# R450B.net
KiCad netlist of a schematic drawn in EAGLE
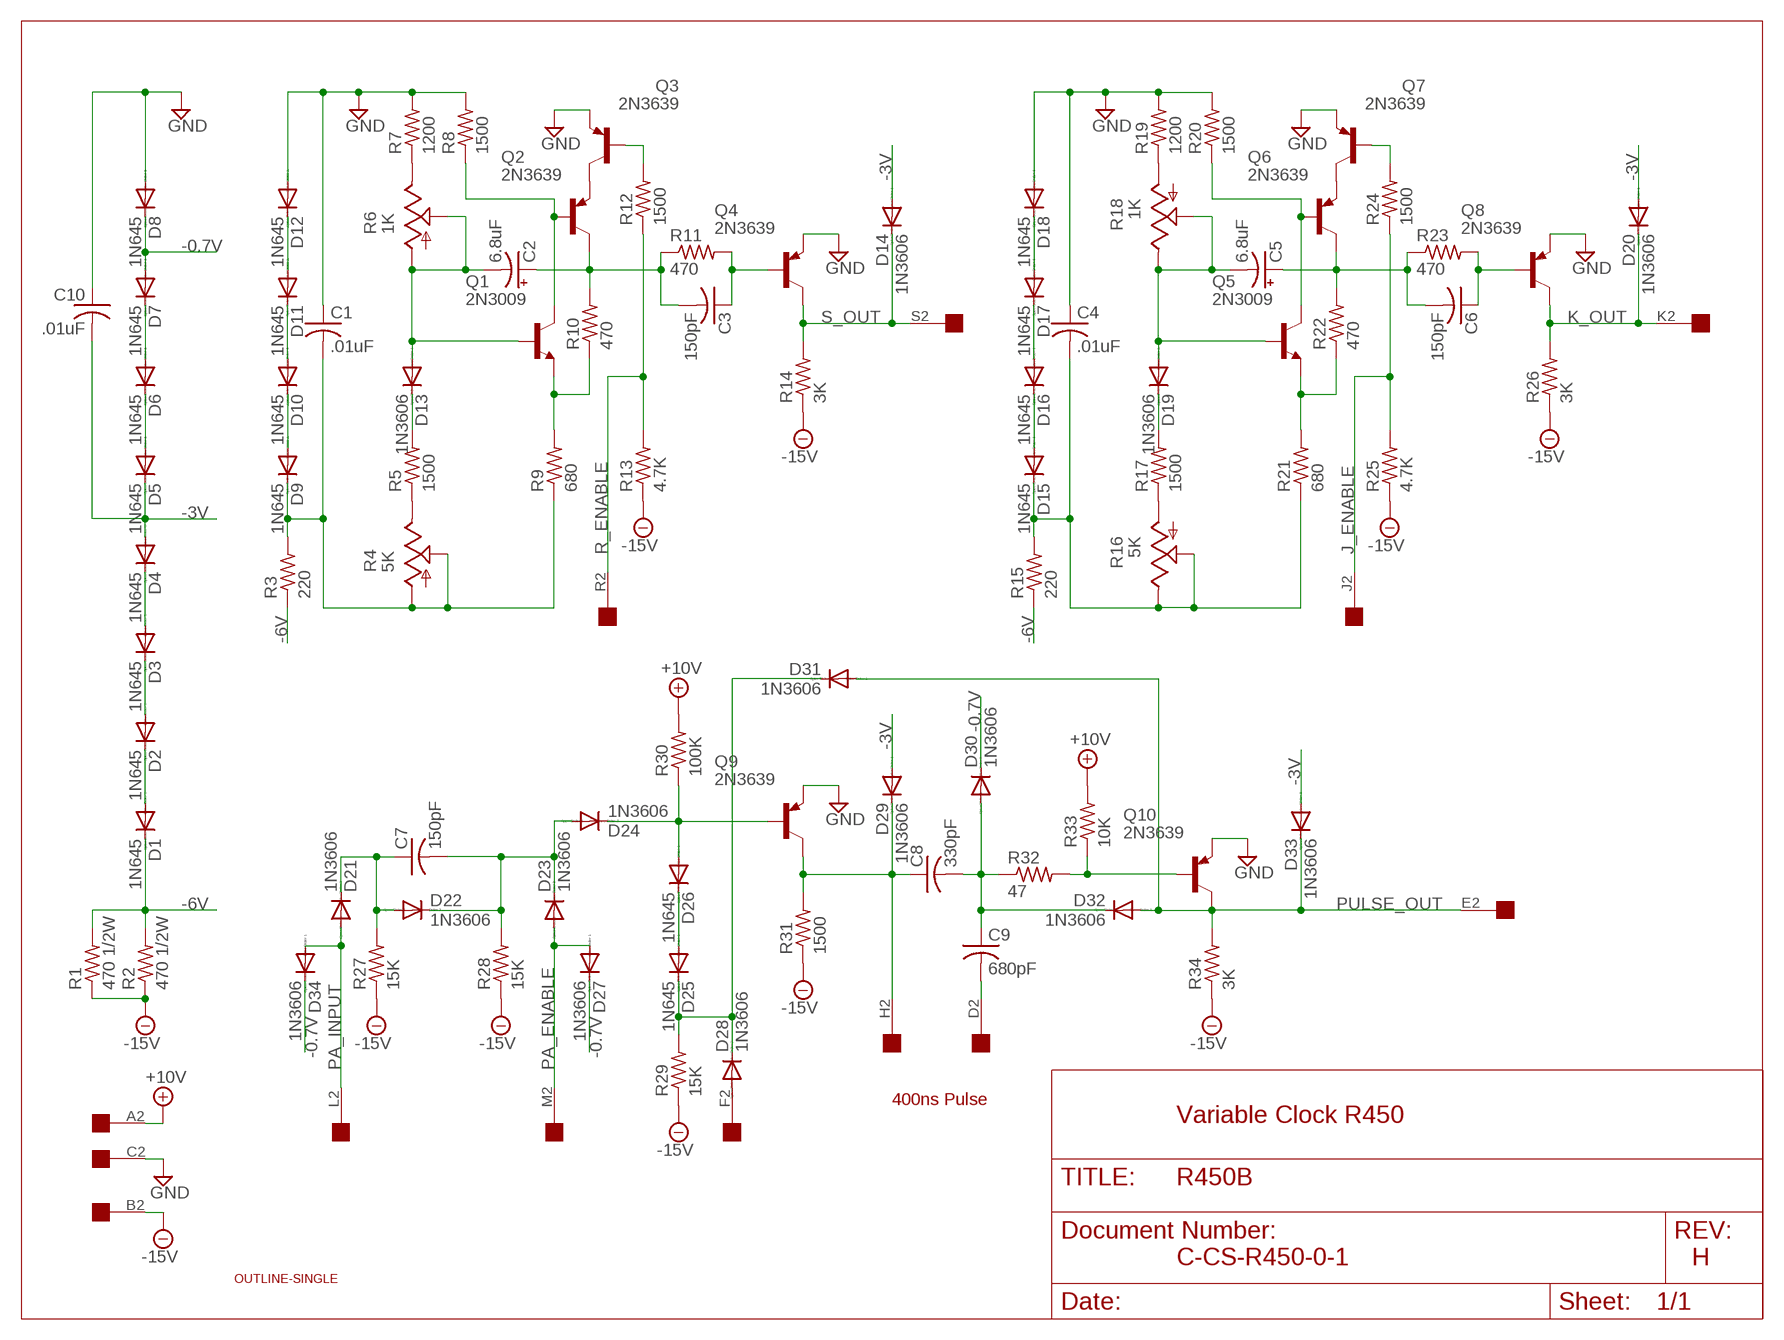
[diagram p0: schematic, sheet 1]

(export (version "E")
  (design (tool "Eeschema 10.0.6"))
  (components
    (comp (ref "C1")
      (value ".01uF")
      (footprint "eagle-import:C063-025X075")
      (libsource (lib "eagle-import") (part "C-US"))
    )
    (comp (ref "C2")
      (value "6.8uF")
      (footprint "eagle-import:E15-5")
      (libsource (lib "eagle-import") (part "CPOL-USE15-5AXIAL"))
    )
    (comp (ref "C3")
      (value "150pF")
      (footprint "eagle-import:C075-032X103")
      (libsource (lib "eagle-import") (part "C-US075-032X103"))
    )
    (comp (ref "C4")
      (value ".01uF")
      (footprint "eagle-import:C063-025X075")
      (libsource (lib "eagle-import") (part "C-US"))
    )
    (comp (ref "C5")
      (value "6.8uF")
      (footprint "eagle-import:E15-5")
      (libsource (lib "eagle-import") (part "CPOL-USE15-5AXIAL"))
    )
    (comp (ref "C6")
      (value "150pF")
      (footprint "eagle-import:C063-025X075")
      (libsource (lib "eagle-import") (part "C-US"))
    )
    (comp (ref "C7")
      (value "150pF")
      (footprint "eagle-import:C063-025X075")
      (libsource (lib "eagle-import") (part "C-US"))
    )
    (comp (ref "C8")
      (value "330pF")
      (footprint "eagle-import:C063-025X075")
      (libsource (lib "eagle-import") (part "C-US"))
    )
    (comp (ref "C9")
      (value "680pF")
      (footprint "eagle-import:C063-025X075")
      (libsource (lib "eagle-import") (part "C-US"))
    )
    (comp (ref "C10")
      (value ".01uF")
      (footprint "eagle-import:C063-025X075")
      (libsource (lib "eagle-import") (part "C-US"))
    )
    (comp (ref "D1")
      (value "1N645")
      (footprint "eagle-import:DO35-10")
      (libsource (lib "eagle-import") (part "1N4148DO35-10"))
    )
    (comp (ref "D2")
      (value "1N645")
      (footprint "eagle-import:DO35-10")
      (libsource (lib "eagle-import") (part "1N4148DO35-10"))
    )
    (comp (ref "D3")
      (value "1N645")
      (footprint "eagle-import:DO35-10")
      (libsource (lib "eagle-import") (part "1N4148DO35-10"))
    )
    (comp (ref "D4")
      (value "1N645")
      (footprint "eagle-import:DO35-10")
      (libsource (lib "eagle-import") (part "1N4148DO35-10"))
    )
    (comp (ref "D5")
      (value "1N645")
      (footprint "eagle-import:DO35-10")
      (libsource (lib "eagle-import") (part "1N4148DO35-10"))
    )
    (comp (ref "D6")
      (value "1N645")
      (footprint "eagle-import:DO35-10")
      (libsource (lib "eagle-import") (part "1N4148DO35-10"))
    )
    (comp (ref "D7")
      (value "1N645")
      (footprint "eagle-import:DO35-10")
      (libsource (lib "eagle-import") (part "1N4148DO35-10"))
    )
    (comp (ref "D8")
      (value "1N645")
      (footprint "eagle-import:DO35-10")
      (libsource (lib "eagle-import") (part "1N4148DO35-10"))
    )
    (comp (ref "D9")
      (value "1N645")
      (footprint "eagle-import:DO35-10")
      (libsource (lib "eagle-import") (part "1N4148DO35-10"))
    )
    (comp (ref "D10")
      (value "1N645")
      (footprint "eagle-import:DO35-10")
      (libsource (lib "eagle-import") (part "1N4148DO35-10"))
    )
    (comp (ref "D11")
      (value "1N645")
      (footprint "eagle-import:DO35-10")
      (libsource (lib "eagle-import") (part "1N4148DO35-10"))
    )
    (comp (ref "D12")
      (value "1N645")
      (footprint "eagle-import:DO35-10")
      (libsource (lib "eagle-import") (part "1N4148DO35-10"))
    )
    (comp (ref "D13")
      (value "1N3606")
      (footprint "eagle-import:DO35-10")
      (libsource (lib "eagle-import") (part "1N4148DO35-10"))
    )
    (comp (ref "D14")
      (value "1N3606")
      (footprint "eagle-import:DO35-10")
      (libsource (lib "eagle-import") (part "1N4148DO35-10"))
    )
    (comp (ref "D15")
      (value "1N645")
      (footprint "eagle-import:DO35-10")
      (libsource (lib "eagle-import") (part "1N4148DO35-10"))
    )
    (comp (ref "D16")
      (value "1N645")
      (footprint "eagle-import:DO35-10")
      (libsource (lib "eagle-import") (part "1N4148DO35-10"))
    )
    (comp (ref "D17")
      (value "1N645")
      (footprint "eagle-import:DO35-10")
      (libsource (lib "eagle-import") (part "1N4148DO35-10"))
    )
    (comp (ref "D18")
      (value "1N645")
      (footprint "eagle-import:DO35-10")
      (libsource (lib "eagle-import") (part "1N4148DO35-10"))
    )
    (comp (ref "D19")
      (value "1N3606")
      (footprint "eagle-import:DO35-10")
      (libsource (lib "eagle-import") (part "1N4148DO35-10"))
    )
    (comp (ref "D20")
      (value "1N3606")
      (footprint "eagle-import:DO35-10")
      (libsource (lib "eagle-import") (part "1N4148DO35-10"))
    )
    (comp (ref "D21")
      (value "1N3606")
      (footprint "eagle-import:DO35-10")
      (libsource (lib "eagle-import") (part "1N4148DO35-10"))
    )
    (comp (ref "D22")
      (value "1N3606")
      (footprint "eagle-import:DO35-10")
      (libsource (lib "eagle-import") (part "1N4148DO35-10"))
    )
    (comp (ref "D23")
      (value "1N3606")
      (footprint "eagle-import:DO35-10")
      (libsource (lib "eagle-import") (part "1N4148DO35-10"))
    )
    (comp (ref "D24")
      (value "1N3606")
      (footprint "eagle-import:DO35-10")
      (libsource (lib "eagle-import") (part "1N4148DO35-10"))
    )
    (comp (ref "D25")
      (value "1N645")
      (footprint "eagle-import:DO35-10")
      (libsource (lib "eagle-import") (part "1N4148DO35-10"))
    )
    (comp (ref "D26")
      (value "1N645")
      (footprint "eagle-import:DO35-10")
      (libsource (lib "eagle-import") (part "1N4148DO35-10"))
    )
    (comp (ref "D27")
      (value "1N3606")
      (footprint "eagle-import:DO35-10")
      (libsource (lib "eagle-import") (part "1N4148DO35-10"))
    )
    (comp (ref "D28")
      (value "1N3606")
      (footprint "eagle-import:DO35-10")
      (libsource (lib "eagle-import") (part "1N4148DO35-10"))
    )
    (comp (ref "D29")
      (value "1N3606")
      (footprint "eagle-import:DO35-10")
      (libsource (lib "eagle-import") (part "1N4148DO35-10"))
    )
    (comp (ref "D30")
      (value "1N3606")
      (footprint "eagle-import:DO35-10")
      (libsource (lib "eagle-import") (part "1N4148DO35-10"))
    )
    (comp (ref "D31")
      (value "1N3606")
      (footprint "eagle-import:DO35-10")
      (libsource (lib "eagle-import") (part "1N4148DO35-10"))
    )
    (comp (ref "D32")
      (value "1N3606")
      (footprint "eagle-import:DO35-10")
      (libsource (lib "eagle-import") (part "1N4148DO35-10"))
    )
    (comp (ref "D33")
      (value "1N3606")
      (footprint "eagle-import:DO35-10")
      (libsource (lib "eagle-import") (part "1N4148DO35-10"))
    )
    (comp (ref "D34")
      (value "1N3606")
      (footprint "eagle-import:DO35-10")
      (libsource (lib "eagle-import") (part "1N4148DO35-10"))
    )
    (comp (ref "Q1")
      (value "2N3009")
      (footprint "eagle-import:TO5")
      (libsource (lib "eagle-import") (part "2N2102"))
    )
    (comp (ref "Q2")
      (value "2N3639")
      (footprint "eagle-import:TO39")
      (libsource (lib "eagle-import") (part "2N2904"))
    )
    (comp (ref "Q3")
      (value "2N3639")
      (footprint "eagle-import:TO39")
      (libsource (lib "eagle-import") (part "2N2904"))
    )
    (comp (ref "Q4")
      (value "2N3639")
      (footprint "eagle-import:TO39")
      (libsource (lib "eagle-import") (part "2N2904"))
    )
    (comp (ref "Q5")
      (value "2N3009")
      (footprint "eagle-import:TO5")
      (libsource (lib "eagle-import") (part "2N2102"))
    )
    (comp (ref "Q6")
      (value "2N3639")
      (footprint "eagle-import:TO39")
      (libsource (lib "eagle-import") (part "2N2904"))
    )
    (comp (ref "Q7")
      (value "2N3639")
      (footprint "eagle-import:TO39")
      (libsource (lib "eagle-import") (part "2N2904"))
    )
    (comp (ref "Q8")
      (value "2N3639")
      (footprint "eagle-import:TO39")
      (libsource (lib "eagle-import") (part "2N2904"))
    )
    (comp (ref "Q9")
      (value "2N3639")
      (footprint "eagle-import:TO39")
      (libsource (lib "eagle-import") (part "2N2904"))
    )
    (comp (ref "Q10")
      (value "2N3639")
      (footprint "eagle-import:TO39")
      (libsource (lib "eagle-import") (part "2N2904"))
    )
    (comp (ref "R1")
      (value "470 1/2W")
      (footprint "eagle-import:0411_15")
      (libsource (lib "eagle-import") (part "R-US_0411/15"))
    )
    (comp (ref "R2")
      (value "470 1/2W")
      (footprint "eagle-import:0411_15")
      (libsource (lib "eagle-import") (part "R-US_0411/15"))
    )
    (comp (ref "R3")
      (value "220")
      (footprint "eagle-import:0207_10")
      (libsource (lib "eagle-import") (part "R-US_0207/10"))
    )
    (comp (ref "R4")
      (value "5K")
      (footprint "eagle-import:CT6")
      (libsource (lib "eagle-import") (part "TRIM_US-CT6"))
    )
    (comp (ref "R5")
      (value "1500")
      (footprint "eagle-import:0207_10")
      (libsource (lib "eagle-import") (part "R-US_0207/10"))
    )
    (comp (ref "R6")
      (value "1K")
      (footprint "eagle-import:CT6")
      (libsource (lib "eagle-import") (part "TRIM_US-CT6"))
    )
    (comp (ref "R7")
      (value "1200")
      (footprint "eagle-import:0207_10")
      (libsource (lib "eagle-import") (part "R-US_0207/10"))
    )
    (comp (ref "R8")
      (value "1500")
      (footprint "eagle-import:0207_10")
      (libsource (lib "eagle-import") (part "R-US_0207/10"))
    )
    (comp (ref "R9")
      (value "680")
      (footprint "eagle-import:0207_10")
      (libsource (lib "eagle-import") (part "R-US_0207/10"))
    )
    (comp (ref "R10")
      (value "470")
      (footprint "eagle-import:0207_10")
      (libsource (lib "eagle-import") (part "R-US_0207/10"))
    )
    (comp (ref "R11")
      (value "470")
      (footprint "eagle-import:0207_10")
      (libsource (lib "eagle-import") (part "R-US_0207/10"))
    )
    (comp (ref "R12")
      (value "1500")
      (footprint "eagle-import:0207_10")
      (libsource (lib "eagle-import") (part "R-US_0207/10"))
    )
    (comp (ref "R13")
      (value "4.7K")
      (footprint "eagle-import:0207_10")
      (libsource (lib "eagle-import") (part "R-US_0207/10"))
    )
    (comp (ref "R14")
      (value "3K")
      (footprint "eagle-import:0207_10")
      (libsource (lib "eagle-import") (part "R-US_0207/10"))
    )
    (comp (ref "R15")
      (value "220")
      (footprint "eagle-import:0207_10")
      (libsource (lib "eagle-import") (part "R-US_0207/10"))
    )
    (comp (ref "R16")
      (value "5K")
      (footprint "eagle-import:CT6")
      (libsource (lib "eagle-import") (part "TRIM_US-CT6"))
    )
    (comp (ref "R17")
      (value "1500")
      (footprint "eagle-import:0207_10")
      (libsource (lib "eagle-import") (part "R-US_0207/10"))
    )
    (comp (ref "R18")
      (value "1K")
      (footprint "eagle-import:CT6")
      (libsource (lib "eagle-import") (part "TRIM_US-CT6"))
    )
    (comp (ref "R19")
      (value "1200")
      (footprint "eagle-import:0207_10")
      (libsource (lib "eagle-import") (part "R-US_0207/10"))
    )
    (comp (ref "R20")
      (value "1500")
      (footprint "eagle-import:0207_10")
      (libsource (lib "eagle-import") (part "R-US_0207/10"))
    )
    (comp (ref "R21")
      (value "680")
      (footprint "eagle-import:0207_10")
      (libsource (lib "eagle-import") (part "R-US_0207/10"))
    )
    (comp (ref "R22")
      (value "470")
      (footprint "eagle-import:0207_10")
      (libsource (lib "eagle-import") (part "R-US_0207/10"))
    )
    (comp (ref "R23")
      (value "470")
      (footprint "eagle-import:0207_10")
      (libsource (lib "eagle-import") (part "R-US_0207/10"))
    )
    (comp (ref "R24")
      (value "1500")
      (footprint "eagle-import:0207_10")
      (libsource (lib "eagle-import") (part "R-US_0207/10"))
    )
    (comp (ref "R25")
      (value "4.7K")
      (footprint "eagle-import:0207_10")
      (libsource (lib "eagle-import") (part "R-US_0207/10"))
    )
    (comp (ref "R26")
      (value "3K")
      (footprint "eagle-import:0207_10")
      (libsource (lib "eagle-import") (part "R-US_0207/10"))
    )
    (comp (ref "R27")
      (value "15K")
      (footprint "eagle-import:0207_10")
      (libsource (lib "eagle-import") (part "R-US_0207/10"))
    )
    (comp (ref "R28")
      (value "15K")
      (footprint "eagle-import:0207_10")
      (libsource (lib "eagle-import") (part "R-US_0207/10"))
    )
    (comp (ref "R29")
      (value "15K")
      (footprint "eagle-import:0207_10")
      (libsource (lib "eagle-import") (part "R-US_0207/10"))
    )
    (comp (ref "R30")
      (value "100K")
      (footprint "eagle-import:0207_10")
      (libsource (lib "eagle-import") (part "R-US_0207/10"))
    )
    (comp (ref "R31")
      (value "1500")
      (footprint "eagle-import:0207_10")
      (libsource (lib "eagle-import") (part "R-US_0207/10"))
    )
    (comp (ref "R32")
      (value "47")
      (footprint "eagle-import:0207_10")
      (libsource (lib "eagle-import") (part "R-US_0207/10"))
    )
    (comp (ref "R33")
      (value "10K")
      (footprint "eagle-import:0207_10")
      (libsource (lib "eagle-import") (part "R-US_0207/10"))
    )
    (comp (ref "R34")
      (value "3K")
      (footprint "eagle-import:0207_10")
      (libsource (lib "eagle-import") (part "R-US_0207/10"))
    )
    (comp (ref "U$1")
      (value "OUTLINE-SINGLE")
      (footprint "eagle-import:SINGLE")
      (libsource (lib "eagle-import") (part "OUTLINE-SINGLE"))
    )
    (comp (ref "U$2")
      (value "EDGE-1")
      (footprint "eagle-import:EDGE-CON1")
      (libsource (lib "eagle-import") (part "EDGE-1"))
    )
  )
  (nets
    (net (code "1") (name "+10V") (class "Default")
      (node (ref "R30") (pin "2") (pinfunction "2_2") (pintype "passive"))
      (node (ref "R33") (pin "2") (pinfunction "2_2") (pintype "passive"))
      (node (ref "U$2") (pin "A2") (pinfunction "1_A2") (pintype "bidirectional"))
    )
    (net (code "2") (name "-15V") (class "Default")
      (node (ref "R1") (pin "1") (pinfunction "1_1") (pintype "passive"))
      (node (ref "R13") (pin "1") (pinfunction "1_1") (pintype "passive"))
      (node (ref "R14") (pin "1") (pinfunction "1_1") (pintype "passive"))
      (node (ref "R2") (pin "1") (pinfunction "1_1") (pintype "passive"))
      (node (ref "R25") (pin "1") (pinfunction "1_1") (pintype "passive"))
      (node (ref "R26") (pin "1") (pinfunction "1_1") (pintype "passive"))
      (node (ref "R27") (pin "1") (pinfunction "1_1") (pintype "passive"))
      (node (ref "R28") (pin "1") (pinfunction "1_1") (pintype "passive"))
      (node (ref "R29") (pin "1") (pinfunction "1_1") (pintype "passive"))
      (node (ref "R31") (pin "1") (pinfunction "1_1") (pintype "passive"))
      (node (ref "R34") (pin "1") (pinfunction "1_1") (pintype "passive"))
      (node (ref "U$2") (pin "B2") (pinfunction "1_B2") (pintype "bidirectional"))
    )
    (net (code "3") (name "/-0.7V") (class "Default")
      (node (ref "D27") (pin "C") (pinfunction "C_C") (pintype "passive"))
      (node (ref "D30") (pin "C") (pinfunction "C_C") (pintype "passive"))
      (node (ref "D34") (pin "C") (pinfunction "C_C") (pintype "passive"))
      (node (ref "D7") (pin "A") (pinfunction "A_A") (pintype "passive"))
      (node (ref "D8") (pin "C") (pinfunction "C_C") (pintype "passive"))
    )
    (net (code "4") (name "/-3V") (class "Default")
      (node (ref "C10") (pin "2") (pinfunction "2_2") (pintype "passive"))
      (node (ref "D14") (pin "A") (pinfunction "A_A") (pintype "passive"))
      (node (ref "D20") (pin "A") (pinfunction "A_A") (pintype "passive"))
      (node (ref "D29") (pin "A") (pinfunction "A_A") (pintype "passive"))
      (node (ref "D33") (pin "A") (pinfunction "A_A") (pintype "passive"))
      (node (ref "D4") (pin "A") (pinfunction "A_A") (pintype "passive"))
      (node (ref "D5") (pin "C") (pinfunction "C_C") (pintype "passive"))
    )
    (net (code "5") (name "/-6V") (class "Default")
      (node (ref "D1") (pin "C") (pinfunction "C_C") (pintype "passive"))
      (node (ref "R1") (pin "2") (pinfunction "2_2") (pintype "passive"))
      (node (ref "R15") (pin "1") (pinfunction "1_1") (pintype "passive"))
      (node (ref "R2") (pin "2") (pinfunction "2_2") (pintype "passive"))
      (node (ref "R3") (pin "1") (pinfunction "1_1") (pintype "passive"))
    )
    (net (code "6") (name "/J_ENABLE") (class "Default")
      (node (ref "R24") (pin "1") (pinfunction "1_1") (pintype "passive"))
      (node (ref "R25") (pin "2") (pinfunction "2_2") (pintype "passive"))
      (node (ref "U$2") (pin "J2") (pinfunction "1_J2") (pintype "bidirectional"))
    )
    (net (code "7") (name "/K_OUT") (class "Default")
      (node (ref "D20") (pin "C") (pinfunction "C_C") (pintype "passive"))
      (node (ref "Q8") (pin "3") (pinfunction "C_3") (pintype "passive"))
      (node (ref "R26") (pin "2") (pinfunction "2_2") (pintype "passive"))
      (node (ref "U$2") (pin "K2") (pinfunction "1_K2") (pintype "bidirectional"))
    )
    (net (code "8") (name "/PA_ENABLE") (class "Default")
      (node (ref "D23") (pin "A") (pinfunction "A_A") (pintype "passive"))
      (node (ref "D27") (pin "A") (pinfunction "A_A") (pintype "passive"))
      (node (ref "U$2") (pin "M2") (pinfunction "1_M2") (pintype "bidirectional"))
    )
    (net (code "9") (name "/PA_INPUT") (class "Default")
      (node (ref "D21") (pin "A") (pinfunction "A_A") (pintype "passive"))
      (node (ref "D34") (pin "A") (pinfunction "A_A") (pintype "passive"))
      (node (ref "U$2") (pin "L2") (pinfunction "1_L2") (pintype "bidirectional"))
    )
    (net (code "10") (name "/PULSE_OUT") (class "Default")
      (node (ref "D31") (pin "A") (pinfunction "A_A") (pintype "passive"))
      (node (ref "D32") (pin "A") (pinfunction "A_A") (pintype "passive"))
      (node (ref "D33") (pin "C") (pinfunction "C_C") (pintype "passive"))
      (node (ref "Q10") (pin "3") (pinfunction "C_3") (pintype "passive"))
      (node (ref "R34") (pin "2") (pinfunction "2_2") (pintype "passive"))
      (node (ref "U$2") (pin "E2") (pinfunction "1_E2") (pintype "bidirectional"))
    )
    (net (code "11") (name "/R_ENABLE") (class "Default")
      (node (ref "R12") (pin "1") (pinfunction "1_1") (pintype "passive"))
      (node (ref "R13") (pin "2") (pinfunction "2_2") (pintype "passive"))
      (node (ref "U$2") (pin "R2") (pinfunction "1_R2") (pintype "bidirectional"))
    )
    (net (code "12") (name "/S_OUT") (class "Default")
      (node (ref "D14") (pin "C") (pinfunction "C_C") (pintype "passive"))
      (node (ref "Q4") (pin "3") (pinfunction "C_3") (pintype "passive"))
      (node (ref "R14") (pin "2") (pinfunction "2_2") (pintype "passive"))
      (node (ref "U$2") (pin "S2") (pinfunction "1_S2") (pintype "bidirectional"))
    )
    (net (code "13") (name "GND") (class "Default")
      (node (ref "C1") (pin "1") (pinfunction "1_1") (pintype "passive"))
      (node (ref "C10") (pin "1") (pinfunction "1_1") (pintype "passive"))
      (node (ref "C4") (pin "1") (pinfunction "1_1") (pintype "passive"))
      (node (ref "D12") (pin "A") (pinfunction "A_A") (pintype "passive"))
      (node (ref "D18") (pin "A") (pinfunction "A_A") (pintype "passive"))
      (node (ref "D8") (pin "A") (pinfunction "A_A") (pintype "passive"))
      (node (ref "Q10") (pin "1") (pinfunction "E_1") (pintype "passive"))
      (node (ref "Q3") (pin "1") (pinfunction "E_1") (pintype "passive"))
      (node (ref "Q4") (pin "1") (pinfunction "E_1") (pintype "passive"))
      (node (ref "Q7") (pin "1") (pinfunction "E_1") (pintype "passive"))
      (node (ref "Q8") (pin "1") (pinfunction "E_1") (pintype "passive"))
      (node (ref "Q9") (pin "1") (pinfunction "E_1") (pintype "passive"))
      (node (ref "R19") (pin "2") (pinfunction "2_2") (pintype "passive"))
      (node (ref "R20") (pin "2") (pinfunction "2_2") (pintype "passive"))
      (node (ref "R7") (pin "2") (pinfunction "2_2") (pintype "passive"))
      (node (ref "R8") (pin "2") (pinfunction "2_2") (pintype "passive"))
      (node (ref "U$2") (pin "C2") (pinfunction "1_C2") (pintype "bidirectional"))
    )
    (net (code "14") (name "Net-(C1-Pad2)") (class "Default")
      (node (ref "C1") (pin "2") (pinfunction "2_2") (pintype "passive"))
      (node (ref "D9") (pin "C") (pinfunction "C_C") (pintype "passive"))
      (node (ref "R3") (pin "2") (pinfunction "2_2") (pintype "passive"))
      (node (ref "R4") (pin "A") (pinfunction "A_A") (pintype "passive"))
      (node (ref "R4") (pin "S") (pinfunction "S_S") (pintype "passive"))
      (node (ref "R9") (pin "1") (pinfunction "1_1") (pintype "passive"))
    )
    (net (code "15") (name "Net-(C4-Pad2)") (class "Default")
      (node (ref "C4") (pin "2") (pinfunction "2_2") (pintype "passive"))
      (node (ref "D15") (pin "C") (pinfunction "C_C") (pintype "passive"))
      (node (ref "R15") (pin "2") (pinfunction "2_2") (pintype "passive"))
      (node (ref "R16") (pin "E") (pinfunction "E_E") (pintype "passive"))
      (node (ref "R16") (pin "S") (pinfunction "S_S") (pintype "passive"))
      (node (ref "R21") (pin "1") (pinfunction "1_1") (pintype "passive"))
    )
    (net (code "16") (name "Net-(C7-Pad1)") (class "Default")
      (node (ref "C7") (pin "1") (pinfunction "1_1") (pintype "passive"))
      (node (ref "D21") (pin "C") (pinfunction "C_C") (pintype "passive"))
      (node (ref "D22") (pin "A") (pinfunction "A_A") (pintype "passive"))
      (node (ref "R27") (pin "2") (pinfunction "2_2") (pintype "passive"))
    )
    (net (code "17") (name "Net-(C7-Pad2)") (class "Default")
      (node (ref "C7") (pin "2") (pinfunction "2_2") (pintype "passive"))
      (node (ref "D22") (pin "C") (pinfunction "C_C") (pintype "passive"))
      (node (ref "D23") (pin "C") (pinfunction "C_C") (pintype "passive"))
      (node (ref "D24") (pin "A") (pinfunction "A_A") (pintype "passive"))
      (node (ref "R28") (pin "2") (pinfunction "2_2") (pintype "passive"))
    )
    (net (code "18") (name "Net-(C8-Pad2)") (class "Default")
      (node (ref "C8") (pin "2") (pinfunction "2_2") (pintype "passive"))
      (node (ref "C9") (pin "1") (pinfunction "1_1") (pintype "passive"))
      (node (ref "D30") (pin "A") (pinfunction "A_A") (pintype "passive"))
      (node (ref "D32") (pin "C") (pinfunction "C_C") (pintype "passive"))
      (node (ref "R32") (pin "1") (pinfunction "1_1") (pintype "passive"))
    )
    (net (code "19") (name "Net-(D1-PadA)") (class "Default")
      (node (ref "D1") (pin "A") (pinfunction "A_A") (pintype "passive"))
      (node (ref "D2") (pin "C") (pinfunction "C_C") (pintype "passive"))
    )
    (net (code "20") (name "Net-(D2-PadA)") (class "Default")
      (node (ref "D2") (pin "A") (pinfunction "A_A") (pintype "passive"))
      (node (ref "D3") (pin "C") (pinfunction "C_C") (pintype "passive"))
    )
    (net (code "21") (name "Net-(D3-PadA)") (class "Default")
      (node (ref "D3") (pin "A") (pinfunction "A_A") (pintype "passive"))
      (node (ref "D4") (pin "C") (pinfunction "C_C") (pintype "passive"))
    )
    (net (code "22") (name "Net-(D5-PadA)") (class "Default")
      (node (ref "D5") (pin "A") (pinfunction "A_A") (pintype "passive"))
      (node (ref "D6") (pin "C") (pinfunction "C_C") (pintype "passive"))
    )
    (net (code "23") (name "Net-(D6-PadA)") (class "Default")
      (node (ref "D6") (pin "A") (pinfunction "A_A") (pintype "passive"))
      (node (ref "D7") (pin "C") (pinfunction "C_C") (pintype "passive"))
    )
    (net (code "24") (name "Net-(D10-PadA)") (class "Default")
      (node (ref "D10") (pin "A") (pinfunction "A_A") (pintype "passive"))
      (node (ref "D11") (pin "C") (pinfunction "C_C") (pintype "passive"))
    )
    (net (code "25") (name "Net-(D10-PadC)") (class "Default")
      (node (ref "D10") (pin "C") (pinfunction "C_C") (pintype "passive"))
      (node (ref "D9") (pin "A") (pinfunction "A_A") (pintype "passive"))
    )
    (net (code "26") (name "Net-(D11-PadA)") (class "Default")
      (node (ref "D11") (pin "A") (pinfunction "A_A") (pintype "passive"))
      (node (ref "D12") (pin "C") (pinfunction "C_C") (pintype "passive"))
    )
    (net (code "27") (name "Net-(D13-PadC)") (class "Default")
      (node (ref "D13") (pin "C") (pinfunction "C_C") (pintype "passive"))
      (node (ref "R5") (pin "2") (pinfunction "2_2") (pintype "passive"))
    )
    (net (code "28") (name "Net-(D15-PadA)") (class "Default")
      (node (ref "D15") (pin "A") (pinfunction "A_A") (pintype "passive"))
      (node (ref "D16") (pin "C") (pinfunction "C_C") (pintype "passive"))
    )
    (net (code "29") (name "Net-(D16-PadA)") (class "Default")
      (node (ref "D16") (pin "A") (pinfunction "A_A") (pintype "passive"))
      (node (ref "D17") (pin "C") (pinfunction "C_C") (pintype "passive"))
    )
    (net (code "30") (name "Net-(D17-PadA)") (class "Default")
      (node (ref "D17") (pin "A") (pinfunction "A_A") (pintype "passive"))
      (node (ref "D18") (pin "C") (pinfunction "C_C") (pintype "passive"))
    )
    (net (code "31") (name "Net-(D19-PadC)") (class "Default")
      (node (ref "D19") (pin "C") (pinfunction "C_C") (pintype "passive"))
      (node (ref "R17") (pin "2") (pinfunction "2_2") (pintype "passive"))
    )
    (net (code "32") (name "Net-(D25-PadA)") (class "Default")
      (node (ref "D25") (pin "A") (pinfunction "A_A") (pintype "passive"))
      (node (ref "D26") (pin "C") (pinfunction "C_C") (pintype "passive"))
    )
    (net (code "33") (name "Net-(D25-PadC)") (class "Default")
      (node (ref "D25") (pin "C") (pinfunction "C_C") (pintype "passive"))
      (node (ref "D28") (pin "C") (pinfunction "C_C") (pintype "passive"))
      (node (ref "D31") (pin "C") (pinfunction "C_C") (pintype "passive"))
      (node (ref "R29") (pin "2") (pinfunction "2_2") (pintype "passive"))
    )
    (net (code "34") (name "Net-(Q1-B)") (class "Default")
      (node (ref "C2") (pin "-") (pinfunction "-_-") (pintype "passive"))
      (node (ref "D13") (pin "A") (pinfunction "A_A") (pintype "passive"))
      (node (ref "Q1") (pin "2") (pinfunction "B_2") (pintype "passive"))
      (node (ref "R6") (pin "A") (pinfunction "A_A") (pintype "passive"))
      (node (ref "R6") (pin "S") (pinfunction "S_S") (pintype "passive"))
    )
    (net (code "35") (name "Net-(Q1-C)") (class "Default")
      (node (ref "Q1") (pin "3") (pinfunction "C_3") (pintype "passive"))
      (node (ref "Q2") (pin "2") (pinfunction "B_2") (pintype "passive"))
      (node (ref "R8") (pin "1") (pinfunction "1_1") (pintype "passive"))
    )
    (net (code "36") (name "Net-(Q1-E)") (class "Default")
      (node (ref "Q1") (pin "1") (pinfunction "E_1") (pintype "passive"))
      (node (ref "R10") (pin "1") (pinfunction "1_1") (pintype "passive"))
      (node (ref "R9") (pin "2") (pinfunction "2_2") (pintype "passive"))
    )
    (net (code "37") (name "Net-(Q2-C)") (class "Default")
      (node (ref "C2") (pin "+") (pinfunction "+_+") (pintype "passive"))
      (node (ref "C3") (pin "2") (pinfunction "2_2") (pintype "passive"))
      (node (ref "Q2") (pin "3") (pinfunction "C_3") (pintype "passive"))
      (node (ref "R10") (pin "2") (pinfunction "2_2") (pintype "passive"))
      (node (ref "R11") (pin "1") (pinfunction "1_1") (pintype "passive"))
    )
    (net (code "38") (name "Net-(Q2-E)") (class "Default")
      (node (ref "Q2") (pin "1") (pinfunction "E_1") (pintype "passive"))
      (node (ref "Q3") (pin "3") (pinfunction "C_3") (pintype "passive"))
    )
    (net (code "39") (name "Net-(Q3-B)") (class "Default")
      (node (ref "Q3") (pin "2") (pinfunction "B_2") (pintype "passive"))
      (node (ref "R12") (pin "2") (pinfunction "2_2") (pintype "passive"))
    )
    (net (code "40") (name "Net-(Q4-B)") (class "Default")
      (node (ref "C3") (pin "1") (pinfunction "1_1") (pintype "passive"))
      (node (ref "Q4") (pin "2") (pinfunction "B_2") (pintype "passive"))
      (node (ref "R11") (pin "2") (pinfunction "2_2") (pintype "passive"))
    )
    (net (code "41") (name "Net-(Q5-B)") (class "Default")
      (node (ref "C5") (pin "-") (pinfunction "-_-") (pintype "passive"))
      (node (ref "D19") (pin "A") (pinfunction "A_A") (pintype "passive"))
      (node (ref "Q5") (pin "2") (pinfunction "B_2") (pintype "passive"))
      (node (ref "R18") (pin "E") (pinfunction "E_E") (pintype "passive"))
      (node (ref "R18") (pin "S") (pinfunction "S_S") (pintype "passive"))
    )
    (net (code "42") (name "Net-(Q5-C)") (class "Default")
      (node (ref "Q5") (pin "3") (pinfunction "C_3") (pintype "passive"))
      (node (ref "Q6") (pin "2") (pinfunction "B_2") (pintype "passive"))
      (node (ref "R20") (pin "1") (pinfunction "1_1") (pintype "passive"))
    )
    (net (code "43") (name "Net-(Q5-E)") (class "Default")
      (node (ref "Q5") (pin "1") (pinfunction "E_1") (pintype "passive"))
      (node (ref "R21") (pin "2") (pinfunction "2_2") (pintype "passive"))
      (node (ref "R22") (pin "1") (pinfunction "1_1") (pintype "passive"))
    )
    (net (code "44") (name "Net-(Q6-C)") (class "Default")
      (node (ref "C5") (pin "+") (pinfunction "+_+") (pintype "passive"))
      (node (ref "C6") (pin "2") (pinfunction "2_2") (pintype "passive"))
      (node (ref "Q6") (pin "3") (pinfunction "C_3") (pintype "passive"))
      (node (ref "R22") (pin "2") (pinfunction "2_2") (pintype "passive"))
      (node (ref "R23") (pin "1") (pinfunction "1_1") (pintype "passive"))
    )
    (net (code "45") (name "Net-(Q6-E)") (class "Default")
      (node (ref "Q6") (pin "1") (pinfunction "E_1") (pintype "passive"))
      (node (ref "Q7") (pin "3") (pinfunction "C_3") (pintype "passive"))
    )
    (net (code "46") (name "Net-(Q7-B)") (class "Default")
      (node (ref "Q7") (pin "2") (pinfunction "B_2") (pintype "passive"))
      (node (ref "R24") (pin "2") (pinfunction "2_2") (pintype "passive"))
    )
    (net (code "47") (name "Net-(Q8-B)") (class "Default")
      (node (ref "C6") (pin "1") (pinfunction "1_1") (pintype "passive"))
      (node (ref "Q8") (pin "2") (pinfunction "B_2") (pintype "passive"))
      (node (ref "R23") (pin "2") (pinfunction "2_2") (pintype "passive"))
    )
    (net (code "48") (name "Net-(Q9-B)") (class "Default")
      (node (ref "D24") (pin "C") (pinfunction "C_C") (pintype "passive"))
      (node (ref "D26") (pin "A") (pinfunction "A_A") (pintype "passive"))
      (node (ref "Q9") (pin "2") (pinfunction "B_2") (pintype "passive"))
      (node (ref "R30") (pin "1") (pinfunction "1_1") (pintype "passive"))
    )
    (net (code "49") (name "Net-(Q9-C)") (class "Default")
      (node (ref "C8") (pin "1") (pinfunction "1_1") (pintype "passive"))
      (node (ref "D29") (pin "C") (pinfunction "C_C") (pintype "passive"))
      (node (ref "Q9") (pin "3") (pinfunction "C_3") (pintype "passive"))
      (node (ref "R31") (pin "2") (pinfunction "2_2") (pintype "passive"))
      (node (ref "U$2") (pin "H2") (pinfunction "1_H2") (pintype "bidirectional"))
    )
    (net (code "50") (name "Net-(Q10-B)") (class "Default")
      (node (ref "Q10") (pin "2") (pinfunction "B_2") (pintype "passive"))
      (node (ref "R32") (pin "2") (pinfunction "2_2") (pintype "passive"))
      (node (ref "R33") (pin "1") (pinfunction "1_1") (pintype "passive"))
    )
    (net (code "51") (name "Net-(R4-PadE)") (class "Default")
      (node (ref "R4") (pin "E") (pinfunction "E_E") (pintype "passive"))
      (node (ref "R5") (pin "1") (pinfunction "1_1") (pintype "passive"))
    )
    (net (code "52") (name "Net-(R6-PadE)") (class "Default")
      (node (ref "R6") (pin "E") (pinfunction "E_E") (pintype "passive"))
      (node (ref "R7") (pin "1") (pinfunction "1_1") (pintype "passive"))
    )
    (net (code "53") (name "Net-(R16-PadA)") (class "Default")
      (node (ref "R16") (pin "A") (pinfunction "A_A") (pintype "passive"))
      (node (ref "R17") (pin "1") (pinfunction "1_1") (pintype "passive"))
    )
    (net (code "54") (name "Net-(R18-PadA)") (class "Default")
      (node (ref "R18") (pin "A") (pinfunction "A_A") (pintype "passive"))
      (node (ref "R19") (pin "1") (pinfunction "1_1") (pintype "passive"))
    )
    (net (code "55") (name "Net-(U$2D-1)") (class "Default")
      (node (ref "C9") (pin "2") (pinfunction "2_2") (pintype "passive"))
      (node (ref "U$2") (pin "D2") (pinfunction "1_D2") (pintype "bidirectional"))
    )
    (net (code "56") (name "Net-(U$2F-1)") (class "Default")
      (node (ref "D28") (pin "A") (pinfunction "A_A") (pintype "passive"))
      (node (ref "U$2") (pin "F2") (pinfunction "1_F2") (pintype "bidirectional"))
    )
  )
)
